# MotorControlCircruit.net
KiCad netlist of a schematic drawn in Altium Designer
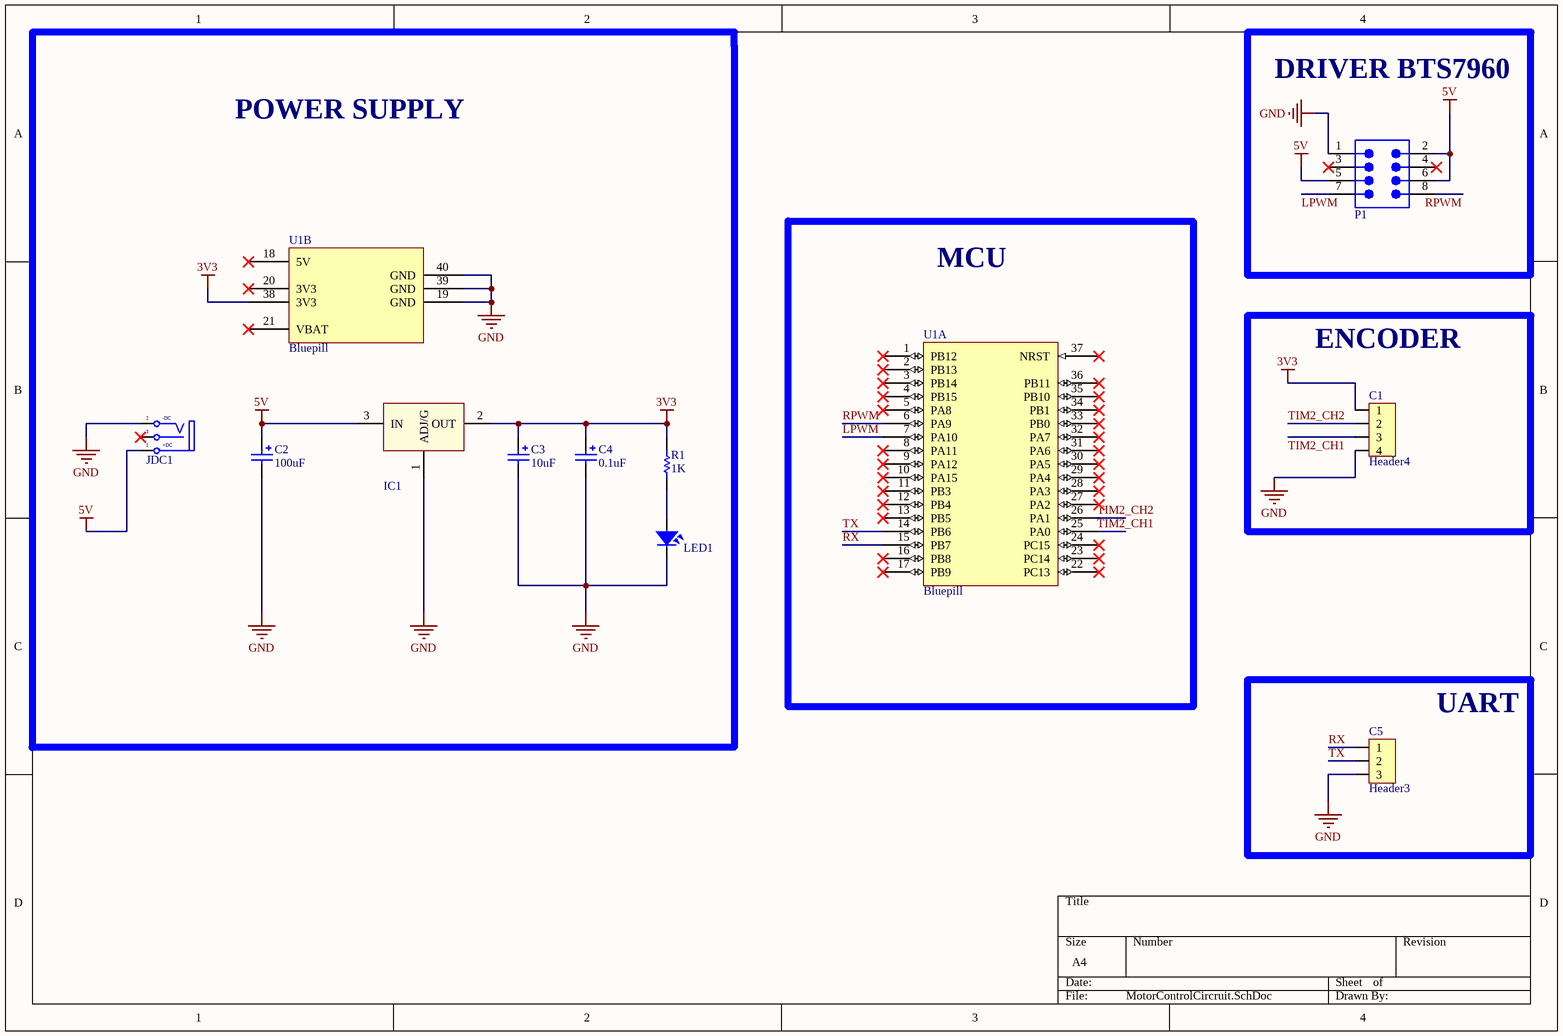
[diagram p0: MotorControlCircruit.SchDoc]

(export (version "E")
  (design (tool "Eeschema 10.0.6"))
  (components
    (comp (ref "C1")
      (value "Header4")
      (footprint "Header4")
      (description "Header IDC, 4 x 1 Pin Vertical 2.54mm Pitch (Non-Boxed, Male)")
      (fields
        (field (name "MANUFACTURER") "Würth Elektronik eiSos GmbH")
        (field (name "PARTNO") "613002143121")
        (field (name "CREATED BY") "Karrer Zheng")
      )
      (libsource (lib "TechMT.VN_Lib_Project v2") (part "Header4"))
    )
    (comp (ref "C2")
      (value "100uF")
      (footprint "CP1.5/3.4")
      (description "Polarized Capacitor (Radial)")
      (fields (field (name "Comment") "Cap Pol"))
      (libsource (lib "PIF_Library") (part "Cap Pol"))
    )
    (comp (ref "C3")
      (value "10uF")
      (footprint "CP1/2.5")
      (description "Polarized Capacitor (Radial)")
      (fields (field (name "Comment") "Cap Pol"))
      (libsource (lib "PIF_Library") (part "Cap Pol"))
    )
    (comp (ref "C4")
      (value "0.1uF")
      (footprint "CP1/2.5")
      (description "Polarized Capacitor (Radial)")
      (fields (field (name "Comment") "Cap Pol"))
      (libsource (lib "PIF_Library") (part "Cap Pol"))
    )
    (comp (ref "C5")
      (value "Header3")
      (footprint "Header3")
      (description "Header IDC, 3 x 1 Pin Vertical 2.54mm Pitch (Non-Boxed, Male)")
      (fields
        (field (name "MANUFACTURER") "Würth Elektronik eiSos GmbH")
        (field (name "PARTNO") "613002143121")
        (field (name "CREATED BY") "Karrer Zheng")
      )
      (libsource (lib "TechMT.VN_Lib_Project v2") (part "Header3"))
    )
    (comp (ref "IC1")
      (value "LM1117")
      (footprint "QTO-220")
      (description "Available in 1.8V, 2.5V, 2.85V, 3.3V, 5V, and  Adjustable Versions")
      (libsource (lib "PIF_Library") (part "LM1117"))
    )
    (comp (ref "JDC1")
      (value "Jack DC")
      (footprint "DC-IN")
      (description "Jack DC input")
      (libsource (lib "PIF_Library") (part "Jack DC"))
    )
    (comp (ref "LED1")
      (value "LED")
      (footprint "LED-5-RED")
      (description "LED Single colour Green and Red")
      (libsource (lib "altium-import") (part "root_0_LED_"))
    )
    (comp (ref "P1")
      (value "61300821121")
      (footprint "61300821121")
      (description "WR-PHD Pin Header, THT, Vertical, pitch 2.54mm, 2 Row, 8P")
      (fields (field (name "MANUFACTURER") "Wurth Elektronik"))
      (libsource (lib "altium-import") (part "root_0_61300821121_"))
    )
    (comp (ref "R1")
      (value "1K")
      (footprint "RES 1/4 W")
      (description "Resistor")
      (fields (field (name "Comment") "RESISTOR"))
      (libsource (lib "PIF_Library") (part "RESISTOR"))
    )
    (comp (ref "U1")
      (value "Bluepill")
      (footprint "Blue Pill")
      (description "STM32F103C8T6")
      (libsource (lib "altium-import") (part "root_0_STM32F103C8T6_"))
    )
  )
  (nets
    (net (code "1") (name "/LPWM") (class "Default")
      (node (ref "P1") (pin "7") (pinfunction "7_7") (pintype "passive"))
      (node (ref "U1") (pin "7") (pinfunction "PA10_7") (pintype "bidirectional"))
    )
    (net (code "2") (name "/RPWM") (class "Default")
      (node (ref "P1") (pin "8") (pinfunction "8_8") (pintype "passive"))
      (node (ref "U1") (pin "6") (pinfunction "PA9_6") (pintype "bidirectional"))
    )
    (net (code "3") (name "/RX") (class "Default")
      (node (ref "C5") (pin "1") (pinfunction "1_1") (pintype "passive"))
      (node (ref "U1") (pin "15") (pinfunction "PB7_15") (pintype "bidirectional"))
    )
    (net (code "4") (name "/TIM2_CH1") (class "Default")
      (node (ref "C1") (pin "3") (pinfunction "3_3") (pintype "passive"))
      (node (ref "U1") (pin "25") (pinfunction "PA0_25") (pintype "bidirectional"))
    )
    (net (code "5") (name "/TIM2_CH2") (class "Default")
      (node (ref "C1") (pin "2") (pinfunction "2_2") (pintype "passive"))
      (node (ref "U1") (pin "26") (pinfunction "PA1_26") (pintype "bidirectional"))
    )
    (net (code "6") (name "/TX") (class "Default")
      (node (ref "C5") (pin "2") (pinfunction "2_2") (pintype "passive"))
      (node (ref "U1") (pin "14") (pinfunction "PB6_14") (pintype "bidirectional"))
    )
    (net (code "7") (name "3V3") (class "Default")
      (node (ref "C1") (pin "1") (pinfunction "1_1") (pintype "passive"))
      (node (ref "C3") (pin "1") (pinfunction "1_1") (pintype "passive"))
      (node (ref "C4") (pin "1") (pinfunction "1_1") (pintype "passive"))
      (node (ref "IC1") (pin "2") (pinfunction "OUT_2") (pintype "passive"))
      (node (ref "R1") (pin "2") (pinfunction "2_2") (pintype "passive"))
      (node (ref "U1") (pin "38") (pinfunction "3V3_38") (pintype "power_in"))
    )
    (net (code "8") (name "5V") (class "Default")
      (node (ref "C2") (pin "1") (pinfunction "1_1") (pintype "passive"))
      (node (ref "IC1") (pin "3") (pinfunction "IN_3") (pintype "passive"))
      (node (ref "JDC1") (pin "1") (pinfunction "T_1") (pintype "passive"))
      (node (ref "P1") (pin "2") (pinfunction "2_2") (pintype "passive"))
      (node (ref "P1") (pin "5") (pinfunction "5_5") (pintype "passive"))
      (node (ref "P1") (pin "6") (pinfunction "6_6") (pintype "passive"))
    )
    (net (code "9") (name "GND") (class "Default")
      (node (ref "C1") (pin "4") (pinfunction "4_4") (pintype "passive"))
      (node (ref "C2") (pin "2") (pinfunction "2_2") (pintype "passive"))
      (node (ref "C3") (pin "2") (pinfunction "2_2") (pintype "passive"))
      (node (ref "C4") (pin "2") (pinfunction "2_2") (pintype "passive"))
      (node (ref "C5") (pin "3") (pinfunction "3_3") (pintype "passive"))
      (node (ref "IC1") (pin "1") (pinfunction "ADJ/G_1") (pintype "passive"))
      (node (ref "JDC1") (pin "2") (pinfunction "TN_2") (pintype "passive"))
      (node (ref "LED1") (pin "2") (pinfunction "2_2") (pintype "passive"))
      (node (ref "P1") (pin "1") (pinfunction "1_1") (pintype "passive"))
      (node (ref "U1") (pin "19") (pinfunction "GND_19") (pintype "power_in"))
      (node (ref "U1") (pin "39") (pinfunction "GND_39") (pintype "power_in"))
      (node (ref "U1") (pin "40") (pinfunction "GND_40") (pintype "power_in"))
    )
    (net (code "10") (name "Net-(LED1-Pad1)") (class "Default")
      (node (ref "LED1") (pin "1") (pinfunction "1_1") (pintype "passive"))
      (node (ref "R1") (pin "1") (pinfunction "1_1") (pintype "passive"))
    )
    (net (code "11") (name "unconnected-(JDC1-S-Pad3)") (class "Default")
      (node (ref "JDC1") (pin "3") (pinfunction "S_3") (pintype "power_in+no_connect"))
    )
    (net (code "12") (name "unconnected-(P1-Pad3)") (class "Default")
      (node (ref "P1") (pin "3") (pinfunction "3_3") (pintype "passive+no_connect"))
    )
    (net (code "13") (name "unconnected-(P1-Pad4)") (class "Default")
      (node (ref "P1") (pin "4") (pinfunction "4_4") (pintype "passive+no_connect"))
    )
    (net (code "14") (name "unconnected-(U1A-NRST-Pad37)") (class "Default")
      (node (ref "U1") (pin "37") (pinfunction "NRST_37") (pintype "input+no_connect"))
    )
    (net (code "15") (name "unconnected-(U1A-PA2-Pad27)") (class "Default")
      (node (ref "U1") (pin "27") (pinfunction "PA2_27") (pintype "bidirectional+no_connect"))
    )
    (net (code "16") (name "unconnected-(U1A-PA3-Pad28)") (class "Default")
      (node (ref "U1") (pin "28") (pinfunction "PA3_28") (pintype "bidirectional+no_connect"))
    )
    (net (code "17") (name "unconnected-(U1A-PA4-Pad29)") (class "Default")
      (node (ref "U1") (pin "29") (pinfunction "PA4_29") (pintype "bidirectional+no_connect"))
    )
    (net (code "18") (name "unconnected-(U1A-PA5-Pad30)") (class "Default")
      (node (ref "U1") (pin "30") (pinfunction "PA5_30") (pintype "bidirectional+no_connect"))
    )
    (net (code "19") (name "unconnected-(U1A-PA6-Pad31)") (class "Default")
      (node (ref "U1") (pin "31") (pinfunction "PA6_31") (pintype "bidirectional+no_connect"))
    )
    (net (code "20") (name "unconnected-(U1A-PA7-Pad32)") (class "Default")
      (node (ref "U1") (pin "32") (pinfunction "PA7_32") (pintype "bidirectional+no_connect"))
    )
    (net (code "21") (name "unconnected-(U1A-PA8-Pad5)") (class "Default")
      (node (ref "U1") (pin "5") (pinfunction "PA8_5") (pintype "bidirectional+no_connect"))
    )
    (net (code "22") (name "unconnected-(U1A-PA11-Pad8)") (class "Default")
      (node (ref "U1") (pin "8") (pinfunction "PA11_8") (pintype "bidirectional+no_connect"))
    )
    (net (code "23") (name "unconnected-(U1A-PA12-Pad9)") (class "Default")
      (node (ref "U1") (pin "9") (pinfunction "PA12_9") (pintype "bidirectional+no_connect"))
    )
    (net (code "24") (name "unconnected-(U1A-PA15-Pad10)") (class "Default")
      (node (ref "U1") (pin "10") (pinfunction "PA15_10") (pintype "bidirectional+no_connect"))
    )
    (net (code "25") (name "unconnected-(U1A-PB0-Pad33)") (class "Default")
      (node (ref "U1") (pin "33") (pinfunction "PB0_33") (pintype "bidirectional+no_connect"))
    )
    (net (code "26") (name "unconnected-(U1A-PB1-Pad34)") (class "Default")
      (node (ref "U1") (pin "34") (pinfunction "PB1_34") (pintype "bidirectional+no_connect"))
    )
    (net (code "27") (name "unconnected-(U1A-PB3-Pad11)") (class "Default")
      (node (ref "U1") (pin "11") (pinfunction "PB3_11") (pintype "bidirectional+no_connect"))
    )
    (net (code "28") (name "unconnected-(U1A-PB4-Pad12)") (class "Default")
      (node (ref "U1") (pin "12") (pinfunction "PB4_12") (pintype "bidirectional+no_connect"))
    )
    (net (code "29") (name "unconnected-(U1A-PB5-Pad13)") (class "Default")
      (node (ref "U1") (pin "13") (pinfunction "PB5_13") (pintype "bidirectional+no_connect"))
    )
    (net (code "30") (name "unconnected-(U1A-PB8-Pad16)") (class "Default")
      (node (ref "U1") (pin "16") (pinfunction "PB8_16") (pintype "bidirectional+no_connect"))
    )
    (net (code "31") (name "unconnected-(U1A-PB9-Pad17)") (class "Default")
      (node (ref "U1") (pin "17") (pinfunction "PB9_17") (pintype "bidirectional+no_connect"))
    )
    (net (code "32") (name "unconnected-(U1A-PB10-Pad35)") (class "Default")
      (node (ref "U1") (pin "35") (pinfunction "PB10_35") (pintype "bidirectional+no_connect"))
    )
    (net (code "33") (name "unconnected-(U1A-PB11-Pad36)") (class "Default")
      (node (ref "U1") (pin "36") (pinfunction "PB11_36") (pintype "bidirectional+no_connect"))
    )
    (net (code "34") (name "unconnected-(U1A-PB12-Pad1)") (class "Default")
      (node (ref "U1") (pin "1") (pinfunction "PB12_1") (pintype "bidirectional+no_connect"))
    )
    (net (code "35") (name "unconnected-(U1A-PB13-Pad2)") (class "Default")
      (node (ref "U1") (pin "2") (pinfunction "PB13_2") (pintype "bidirectional+no_connect"))
    )
    (net (code "36") (name "unconnected-(U1A-PB14-Pad3)") (class "Default")
      (node (ref "U1") (pin "3") (pinfunction "PB14_3") (pintype "bidirectional+no_connect"))
    )
    (net (code "37") (name "unconnected-(U1A-PB15-Pad4)") (class "Default")
      (node (ref "U1") (pin "4") (pinfunction "PB15_4") (pintype "bidirectional+no_connect"))
    )
    (net (code "38") (name "unconnected-(U1A-PC13-Pad22)") (class "Default")
      (node (ref "U1") (pin "22") (pinfunction "PC13_22") (pintype "bidirectional+no_connect"))
    )
    (net (code "39") (name "unconnected-(U1A-PC14-Pad23)") (class "Default")
      (node (ref "U1") (pin "23") (pinfunction "PC14_23") (pintype "bidirectional+no_connect"))
    )
    (net (code "40") (name "unconnected-(U1A-PC15-Pad24)") (class "Default")
      (node (ref "U1") (pin "24") (pinfunction "PC15_24") (pintype "bidirectional+no_connect"))
    )
    (net (code "41") (name "unconnected-(U1B-3V3-Pad20)") (class "Default")
      (node (ref "U1") (pin "20") (pinfunction "3V3_20") (pintype "power_in+no_connect"))
    )
    (net (code "42") (name "unconnected-(U1B-5V-Pad18)") (class "Default")
      (node (ref "U1") (pin "18") (pinfunction "5V_18") (pintype "power_in+no_connect"))
    )
    (net (code "43") (name "unconnected-(U1B-VBAT-Pad21)") (class "Default")
      (node (ref "U1") (pin "21") (pinfunction "VBAT_21") (pintype "power_in+no_connect"))
    )
  )
)
